# cnc_1_0_0.net
KiCad netlist of a schematic drawn in EAGLE
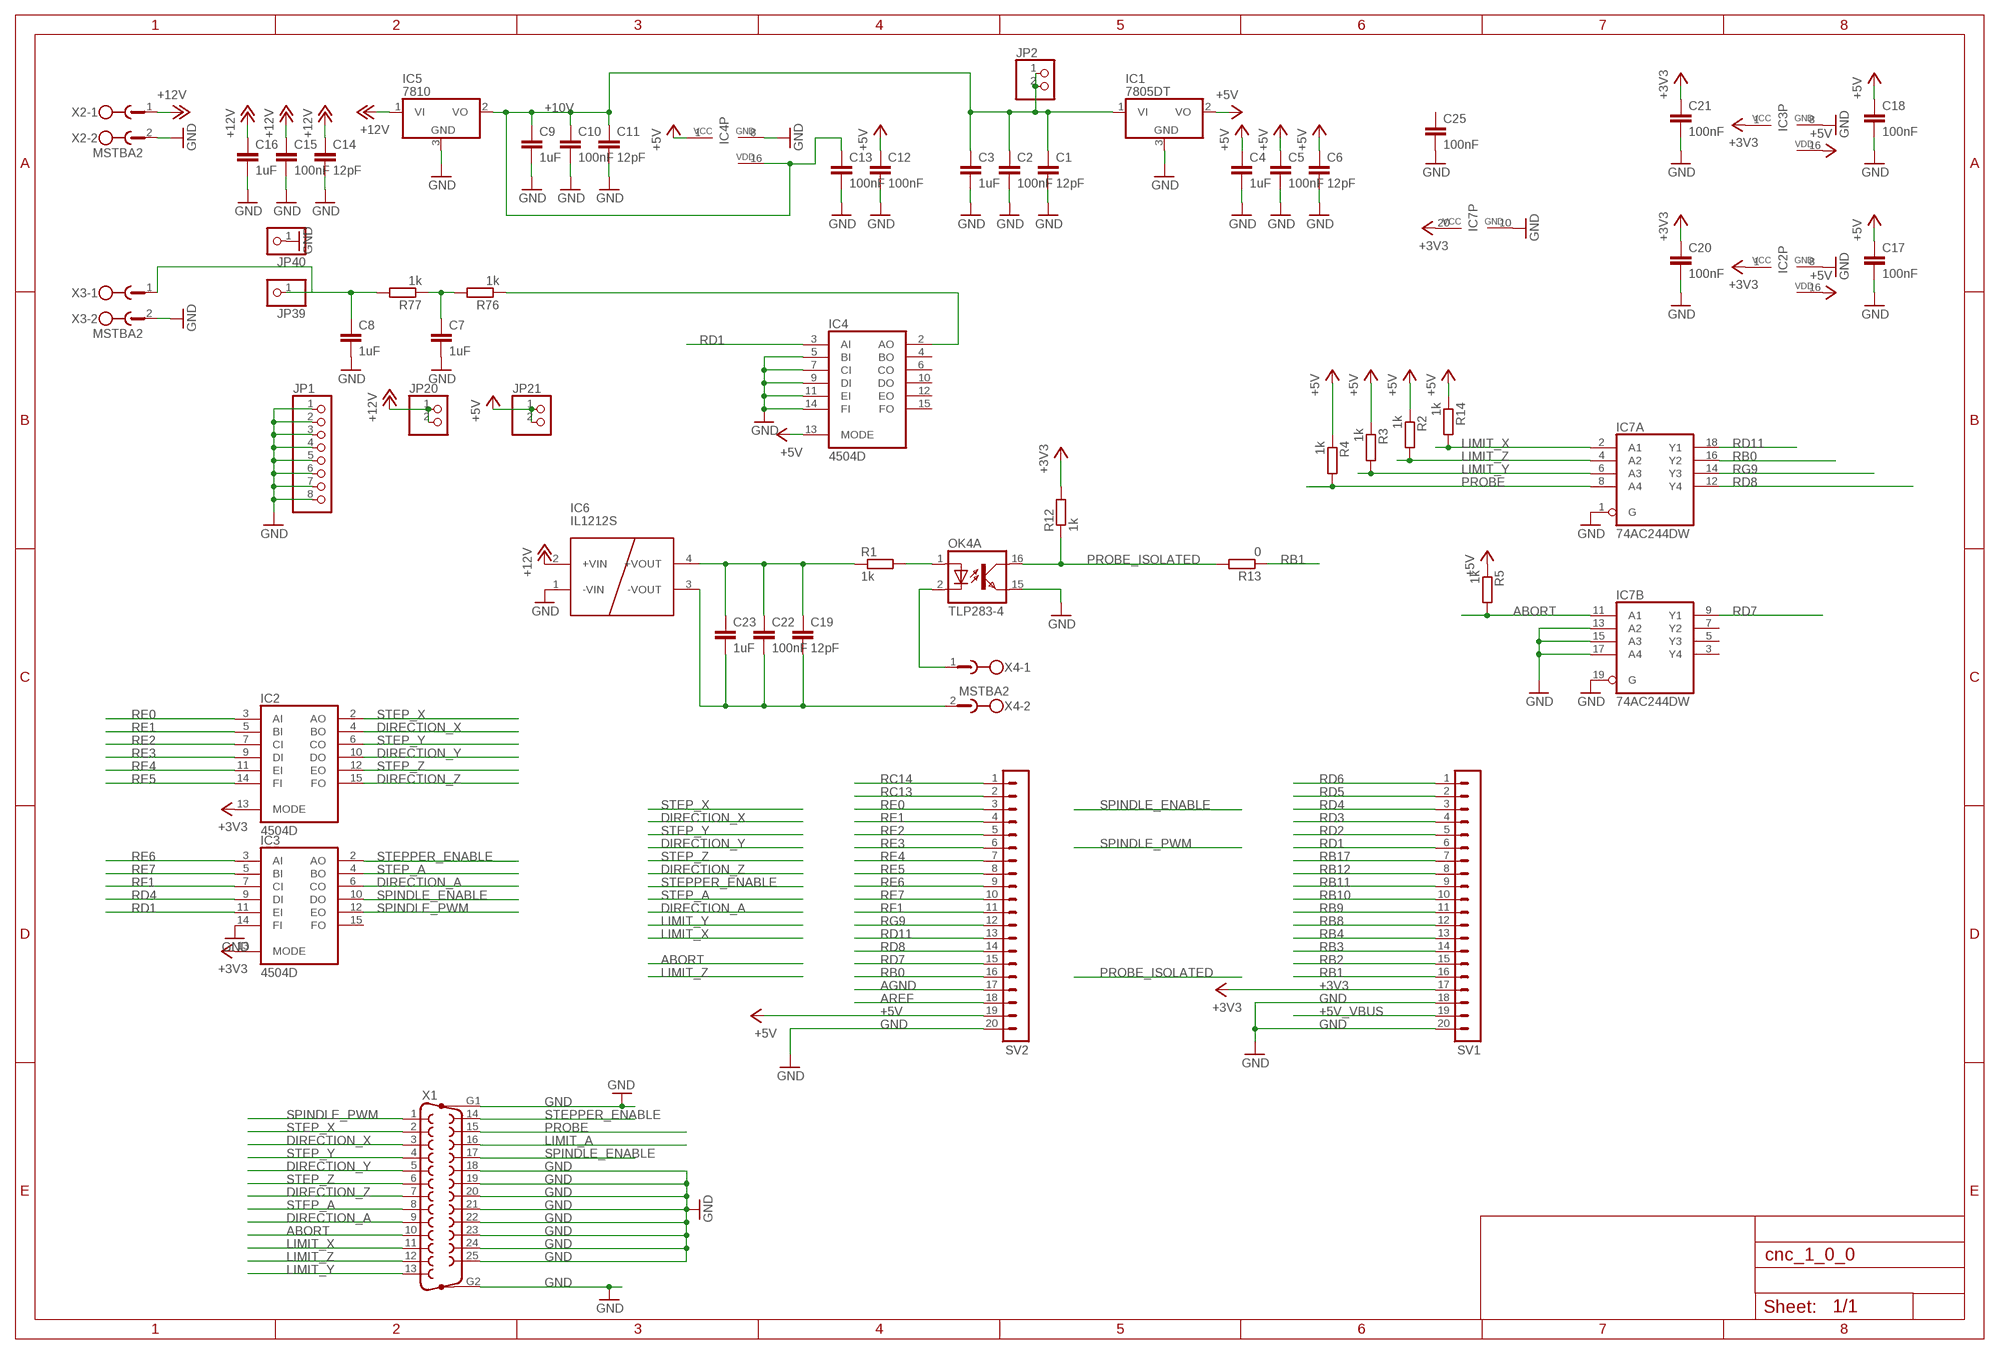
[diagram p0: schematic, sheet 1]

(export (version "E")
  (design (tool "Eeschema 10.0.6"))
  (components
    (comp (ref "C1")
      (value "12pF")
      (footprint "eagle-import:C0805K")
      (libsource (lib "eagle-import") (part "C-EUC0805K"))
    )
    (comp (ref "C2")
      (value "100nF")
      (footprint "eagle-import:C0805K")
      (libsource (lib "eagle-import") (part "C-EUC0805K"))
    )
    (comp (ref "C3")
      (value "1uF")
      (footprint "eagle-import:C0805K")
      (libsource (lib "eagle-import") (part "C-EUC0805K"))
    )
    (comp (ref "C4")
      (value "1uF")
      (footprint "eagle-import:C0805K")
      (libsource (lib "eagle-import") (part "C-EUC0805K"))
    )
    (comp (ref "C5")
      (value "100nF")
      (footprint "eagle-import:C0805K")
      (libsource (lib "eagle-import") (part "C-EUC0805K"))
    )
    (comp (ref "C6")
      (value "12pF")
      (footprint "eagle-import:C0805K")
      (libsource (lib "eagle-import") (part "C-EUC0805K"))
    )
    (comp (ref "C7")
      (value "1uF")
      (footprint "eagle-import:C0805K")
      (libsource (lib "eagle-import") (part "C-EUC0805K"))
    )
    (comp (ref "C8")
      (value "1uF")
      (footprint "eagle-import:C0805K")
      (libsource (lib "eagle-import") (part "C-EUC0805K"))
    )
    (comp (ref "C9")
      (value "1uF")
      (footprint "eagle-import:C0805K")
      (libsource (lib "eagle-import") (part "C-EUC0805K"))
    )
    (comp (ref "C10")
      (value "100nF")
      (footprint "eagle-import:C0805K")
      (libsource (lib "eagle-import") (part "C-EUC0805K"))
    )
    (comp (ref "C11")
      (value "12pF")
      (footprint "eagle-import:C0805K")
      (libsource (lib "eagle-import") (part "C-EUC0805K"))
    )
    (comp (ref "C12")
      (value "100nF")
      (footprint "eagle-import:C0805K")
      (libsource (lib "eagle-import") (part "C-EUC0805K"))
    )
    (comp (ref "C13")
      (value "100nF")
      (footprint "eagle-import:C0805K")
      (libsource (lib "eagle-import") (part "C-EUC0805K"))
    )
    (comp (ref "C14")
      (value "12pF")
      (footprint "eagle-import:C0805K")
      (libsource (lib "eagle-import") (part "C-EUC0805K"))
    )
    (comp (ref "C15")
      (value "100nF")
      (footprint "eagle-import:C0805K")
      (libsource (lib "eagle-import") (part "C-EUC0805K"))
    )
    (comp (ref "C16")
      (value "1uF")
      (footprint "eagle-import:C0805K")
      (libsource (lib "eagle-import") (part "C-EUC0805K"))
    )
    (comp (ref "C17")
      (value "100nF")
      (footprint "eagle-import:C0805K")
      (libsource (lib "eagle-import") (part "C-EUC0805K"))
    )
    (comp (ref "C18")
      (value "100nF")
      (footprint "eagle-import:C0805K")
      (libsource (lib "eagle-import") (part "C-EUC0805K"))
    )
    (comp (ref "C19")
      (value "12pF")
      (footprint "eagle-import:C0805K")
      (libsource (lib "eagle-import") (part "C-EUC0805K"))
    )
    (comp (ref "C20")
      (value "100nF")
      (footprint "eagle-import:C0805K")
      (libsource (lib "eagle-import") (part "C-EUC0805K"))
    )
    (comp (ref "C21")
      (value "100nF")
      (footprint "eagle-import:C0805K")
      (libsource (lib "eagle-import") (part "C-EUC0805K"))
    )
    (comp (ref "C22")
      (value "100nF")
      (footprint "eagle-import:C0805K")
      (libsource (lib "eagle-import") (part "C-EUC0805K"))
    )
    (comp (ref "C23")
      (value "1uF")
      (footprint "eagle-import:C0805K")
      (libsource (lib "eagle-import") (part "C-EUC0805K"))
    )
    (comp (ref "C25")
      (value "100nF")
      (footprint "eagle-import:C0805K")
      (libsource (lib "eagle-import") (part "C-EUC0805K"))
    )
    (comp (ref "IC1")
      (value "7805DT")
      (footprint "eagle-import:TO252")
      (libsource (lib "eagle-import") (part "78DT05"))
    )
    (comp (ref "IC2")
      (value "4504D")
      (footprint "eagle-import:SO16")
      (libsource (lib "eagle-import") (part "4504D"))
    )
    (comp (ref "IC3")
      (value "4504D")
      (footprint "eagle-import:SO16")
      (libsource (lib "eagle-import") (part "4504D"))
    )
    (comp (ref "IC4")
      (value "4504D")
      (footprint "eagle-import:SO16")
      (libsource (lib "eagle-import") (part "4504D"))
    )
    (comp (ref "IC5")
      (value "7810")
      (footprint "eagle-import:TO252")
      (libsource (lib "eagle-import") (part "78DT05"))
    )
    (comp (ref "IC6")
      (value "IL1212S")
      (footprint "eagle-import:SIL4")
      (libsource (lib "eagle-import") (part "IL0512S"))
    )
    (comp (ref "IC7")
      (value "74AC244DW")
      (footprint "eagle-import:SO20W")
      (libsource (lib "eagle-import") (part "74244DWAC"))
    )
    (comp (ref "JP1")
      (value "PINHD-1X8")
      (footprint "eagle-import:1X08")
      (libsource (lib "eagle-import") (part "PINHD-1X8"))
    )
    (comp (ref "JP2")
      (value "PINHD-1X2")
      (footprint "eagle-import:1X02")
      (libsource (lib "eagle-import") (part "PINHD-1X2"))
    )
    (comp (ref "JP20")
      (value "PINHD-1X2")
      (footprint "eagle-import:1X02")
      (libsource (lib "eagle-import") (part "PINHD-1X2"))
    )
    (comp (ref "JP21")
      (value "PINHD-1X2")
      (footprint "eagle-import:1X02")
      (libsource (lib "eagle-import") (part "PINHD-1X2"))
    )
    (comp (ref "JP39")
      (value "PINHD-1X1")
      (footprint "eagle-import:1X01")
      (libsource (lib "eagle-import") (part "PINHD-1X1"))
    )
    (comp (ref "JP40")
      (value "PINHD-1X1")
      (footprint "eagle-import:1X01")
      (libsource (lib "eagle-import") (part "PINHD-1X1"))
    )
    (comp (ref "OK4")
      (value "TLP283-4")
      (footprint "eagle-import:MINI-FLAT-16")
      (libsource (lib "eagle-import") (part "TLP283-4"))
    )
    (comp (ref "R1")
      (value "1k")
      (footprint "eagle-import:R0805")
      (libsource (lib "eagle-import") (part "R-EU_R0805"))
    )
    (comp (ref "R2")
      (value "1k")
      (footprint "eagle-import:R0805")
      (libsource (lib "eagle-import") (part "R-EU_R0805"))
    )
    (comp (ref "R3")
      (value "1k")
      (footprint "eagle-import:R0805")
      (libsource (lib "eagle-import") (part "R-EU_R0805"))
    )
    (comp (ref "R4")
      (value "1k")
      (footprint "eagle-import:R0805")
      (libsource (lib "eagle-import") (part "R-EU_R0805"))
    )
    (comp (ref "R5")
      (value "1k")
      (footprint "eagle-import:R0805")
      (libsource (lib "eagle-import") (part "R-EU_R0805"))
    )
    (comp (ref "R12")
      (value "1k")
      (footprint "eagle-import:R0805")
      (libsource (lib "eagle-import") (part "R-EU_R0805"))
    )
    (comp (ref "R13")
      (value "0")
      (footprint "eagle-import:R0805")
      (libsource (lib "eagle-import") (part "R-EU_R0805"))
    )
    (comp (ref "R14")
      (value "1k")
      (footprint "eagle-import:R0805")
      (libsource (lib "eagle-import") (part "R-EU_R0805"))
    )
    (comp (ref "R76")
      (value "1k")
      (footprint "eagle-import:R0805")
      (libsource (lib "eagle-import") (part "R-EU_R0805"))
    )
    (comp (ref "R77")
      (value "1k")
      (footprint "eagle-import:R0805")
      (libsource (lib "eagle-import") (part "R-EU_R0805"))
    )
    (comp (ref "SV1")
      (value "MA20-1")
      (footprint "eagle-import:MA20-1")
      (libsource (lib "eagle-import") (part "MA20-1"))
    )
    (comp (ref "SV2")
      (value "MA20-1")
      (footprint "eagle-import:MA20-1")
      (libsource (lib "eagle-import") (part "MA20-1"))
    )
    (comp (ref "X1")
      (value "F25HP")
      (footprint "eagle-import:F25HP")
      (libsource (lib "eagle-import") (part "F25HP"))
    )
    (comp (ref "X2")
      (value "MSTBA2")
      (footprint "eagle-import:MSTBA2")
      (fields (field (name "MF") "FARNELL") (field (name "MPN") "1757242"))
      (libsource (lib "eagle-import") (part "MSTBA2"))
    )
    (comp (ref "X3")
      (value "MSTBA2")
      (footprint "eagle-import:MSTBA2")
      (fields
        (field (name "MF") "FARNELL")
        (field (name "MPN") "1757242")
        (field (name "MF_1") "FARNELL")
        (field (name "MPN_1") "1757242")
        (field (name "OC_FARNELL") "3705171")
        (field (name "OC_NEWARK") "71C4161")
      )
      (libsource (lib "eagle-import") (part "MSTBA2"))
    )
    (comp (ref "X4")
      (value "MSTBA2")
      (footprint "eagle-import:MSTBA2")
      (fields
        (field (name "MF") "FARNELL")
        (field (name "MPN") "1757242")
        (field (name "MF_1") "FARNELL")
        (field (name "MPN_1") "1757242")
        (field (name "OC_FARNELL") "3705171")
        (field (name "OC_NEWARK") "71C4161")
      )
      (libsource (lib "eagle-import") (part "MSTBA2"))
    )
  )
  (nets
    (net (code "1") (name "+3V3") (class "Default")
      (node (ref "C20") (pin "1") (pinfunction "1_1") (pintype "passive"))
      (node (ref "C21") (pin "1") (pinfunction "1_1") (pintype "passive"))
      (node (ref "IC2") (pin "1") (pinfunction "VCC_1") (pintype "power_in"))
      (node (ref "IC2") (pin "13") (pinfunction "MODE_13") (pintype "input"))
      (node (ref "IC3") (pin "1") (pinfunction "VCC_1") (pintype "power_in"))
      (node (ref "IC3") (pin "13") (pinfunction "MODE_13") (pintype "input"))
      (node (ref "IC7") (pin "20") (pinfunction "VCC_20") (pintype "power_in"))
      (node (ref "R12") (pin "2") (pinfunction "2_2") (pintype "passive"))
      (node (ref "SV1") (pin "17") (pinfunction "17_17") (pintype "passive"))
    )
    (net (code "2") (name "+5V") (class "Default")
      (node (ref "C12") (pin "1") (pinfunction "1_1") (pintype "passive"))
      (node (ref "C17") (pin "1") (pinfunction "1_1") (pintype "passive"))
      (node (ref "C18") (pin "1") (pinfunction "1_1") (pintype "passive"))
      (node (ref "C4") (pin "1") (pinfunction "1_1") (pintype "passive"))
      (node (ref "C5") (pin "1") (pinfunction "1_1") (pintype "passive"))
      (node (ref "C6") (pin "1") (pinfunction "1_1") (pintype "passive"))
      (node (ref "IC1") (pin "2") (pinfunction "VO_2") (pintype "passive"))
      (node (ref "IC2") (pin "16") (pinfunction "VDD_16") (pintype "power_in"))
      (node (ref "IC3") (pin "16") (pinfunction "VDD_16") (pintype "power_in"))
      (node (ref "IC4") (pin "1") (pinfunction "VCC_1") (pintype "power_in"))
      (node (ref "IC4") (pin "13") (pinfunction "MODE_13") (pintype "input"))
      (node (ref "JP21") (pin "1") (pinfunction "1_1") (pintype "passive"))
      (node (ref "JP21") (pin "2") (pinfunction "2_2") (pintype "passive"))
      (node (ref "R14") (pin "1") (pinfunction "1_1") (pintype "passive"))
      (node (ref "R2") (pin "1") (pinfunction "1_1") (pintype "passive"))
      (node (ref "R3") (pin "1") (pinfunction "1_1") (pintype "passive"))
      (node (ref "R4") (pin "1") (pinfunction "1_1") (pintype "passive"))
      (node (ref "R5") (pin "1") (pinfunction "1_1") (pintype "passive"))
      (node (ref "SV2") (pin "19") (pinfunction "19_19") (pintype "passive"))
    )
    (net (code "3") (name "+12V") (class "Default")
      (node (ref "C14") (pin "1") (pinfunction "1_1") (pintype "passive"))
      (node (ref "C15") (pin "1") (pinfunction "1_1") (pintype "passive"))
      (node (ref "C16") (pin "1") (pinfunction "1_1") (pintype "passive"))
      (node (ref "IC5") (pin "1") (pinfunction "VI_1") (pintype "input"))
      (node (ref "IC6") (pin "2") (pinfunction "+VIN_2") (pintype "bidirectional"))
      (node (ref "JP20") (pin "1") (pinfunction "1_1") (pintype "passive"))
      (node (ref "JP20") (pin "2") (pinfunction "2_2") (pintype "passive"))
      (node (ref "X2") (pin "1") (pinfunction "1_1") (pintype "passive"))
    )
    (net (code "4") (name "/+5V_VBUS") (class "Default")
      (node (ref "SV1") (pin "19") (pinfunction "19_19") (pintype "passive"))
    )
    (net (code "5") (name "/+10V") (class "Default")
      (node (ref "C1") (pin "1") (pinfunction "1_1") (pintype "passive"))
      (node (ref "C10") (pin "1") (pinfunction "1_1") (pintype "passive"))
      (node (ref "C11") (pin "1") (pinfunction "1_1") (pintype "passive"))
      (node (ref "C13") (pin "1") (pinfunction "1_1") (pintype "passive"))
      (node (ref "C2") (pin "1") (pinfunction "1_1") (pintype "passive"))
      (node (ref "C3") (pin "1") (pinfunction "1_1") (pintype "passive"))
      (node (ref "C9") (pin "1") (pinfunction "1_1") (pintype "passive"))
      (node (ref "IC1") (pin "1") (pinfunction "VI_1") (pintype "input"))
      (node (ref "IC4") (pin "16") (pinfunction "VDD_16") (pintype "power_in"))
      (node (ref "IC5") (pin "2") (pinfunction "VO_2") (pintype "passive"))
      (node (ref "JP2") (pin "1") (pinfunction "1_1") (pintype "passive"))
      (node (ref "JP2") (pin "2") (pinfunction "2_2") (pintype "passive"))
    )
    (net (code "6") (name "/ABORT") (class "Default")
      (node (ref "IC7") (pin "11") (pinfunction "A1_11") (pintype "input"))
      (node (ref "R5") (pin "2") (pinfunction "2_2") (pintype "passive"))
      (node (ref "X1") (pin "10") (pinfunction "10_10") (pintype "passive"))
    )
    (net (code "7") (name "/AGND") (class "Default")
      (node (ref "SV2") (pin "17") (pinfunction "17_17") (pintype "passive"))
    )
    (net (code "8") (name "/AREF") (class "Default")
      (node (ref "SV2") (pin "18") (pinfunction "18_18") (pintype "passive"))
    )
    (net (code "9") (name "/DIRECTION_A") (class "Default")
      (node (ref "IC3") (pin "6") (pinfunction "CO_6") (pintype "output"))
      (node (ref "X1") (pin "9") (pinfunction "9_9") (pintype "passive"))
    )
    (net (code "10") (name "/DIRECTION_X") (class "Default")
      (node (ref "IC2") (pin "4") (pinfunction "BO_4") (pintype "output"))
      (node (ref "X1") (pin "3") (pinfunction "3_3") (pintype "passive"))
    )
    (net (code "11") (name "/DIRECTION_Y") (class "Default")
      (node (ref "IC2") (pin "10") (pinfunction "DO_10") (pintype "output"))
      (node (ref "X1") (pin "5") (pinfunction "5_5") (pintype "passive"))
    )
    (net (code "12") (name "/DIRECTION_Z") (class "Default")
      (node (ref "IC2") (pin "15") (pinfunction "FO_15") (pintype "output"))
      (node (ref "X1") (pin "7") (pinfunction "7_7") (pintype "passive"))
    )
    (net (code "13") (name "/LIMIT_A") (class "Default")
      (node (ref "X1") (pin "16") (pinfunction "16_16") (pintype "passive"))
    )
    (net (code "14") (name "/LIMIT_X") (class "Default")
      (node (ref "IC7") (pin "2") (pinfunction "A1_2") (pintype "input"))
      (node (ref "R14") (pin "2") (pinfunction "2_2") (pintype "passive"))
      (node (ref "X1") (pin "11") (pinfunction "11_11") (pintype "passive"))
    )
    (net (code "15") (name "/LIMIT_Y") (class "Default")
      (node (ref "IC7") (pin "6") (pinfunction "A3_6") (pintype "input"))
      (node (ref "R3") (pin "2") (pinfunction "2_2") (pintype "passive"))
      (node (ref "X1") (pin "13") (pinfunction "13_13") (pintype "passive"))
    )
    (net (code "16") (name "/LIMIT_Z") (class "Default")
      (node (ref "IC7") (pin "4") (pinfunction "A2_4") (pintype "input"))
      (node (ref "R2") (pin "2") (pinfunction "2_2") (pintype "passive"))
      (node (ref "X1") (pin "12") (pinfunction "12_12") (pintype "passive"))
    )
    (net (code "17") (name "/PROBE") (class "Default")
      (node (ref "IC7") (pin "8") (pinfunction "A4_8") (pintype "input"))
      (node (ref "R4") (pin "2") (pinfunction "2_2") (pintype "passive"))
      (node (ref "X1") (pin "15") (pinfunction "15_15") (pintype "passive"))
    )
    (net (code "18") (name "/PROBE_ISOLATED") (class "Default")
      (node (ref "OK4") (pin "16") (pinfunction "COL_16") (pintype "passive"))
      (node (ref "R12") (pin "1") (pinfunction "1_1") (pintype "passive"))
      (node (ref "R13") (pin "2") (pinfunction "2_2") (pintype "passive"))
    )
    (net (code "19") (name "/RB0") (class "Default")
      (node (ref "IC7") (pin "16") (pinfunction "Y2_16") (pintype "tri_state"))
      (node (ref "SV2") (pin "16") (pinfunction "16_16") (pintype "passive"))
    )
    (net (code "20") (name "/RB1") (class "Default")
      (node (ref "R13") (pin "1") (pinfunction "1_1") (pintype "passive"))
      (node (ref "SV1") (pin "16") (pinfunction "16_16") (pintype "passive"))
    )
    (net (code "21") (name "/RB2") (class "Default")
      (node (ref "SV1") (pin "15") (pinfunction "15_15") (pintype "passive"))
    )
    (net (code "22") (name "/RB3") (class "Default")
      (node (ref "SV1") (pin "14") (pinfunction "14_14") (pintype "passive"))
    )
    (net (code "23") (name "/RB4") (class "Default")
      (node (ref "SV1") (pin "13") (pinfunction "13_13") (pintype "passive"))
    )
    (net (code "24") (name "/RB8") (class "Default")
      (node (ref "SV1") (pin "12") (pinfunction "12_12") (pintype "passive"))
    )
    (net (code "25") (name "/RB9") (class "Default")
      (node (ref "SV1") (pin "11") (pinfunction "11_11") (pintype "passive"))
    )
    (net (code "26") (name "/RB10") (class "Default")
      (node (ref "SV1") (pin "10") (pinfunction "10_10") (pintype "passive"))
    )
    (net (code "27") (name "/RB11") (class "Default")
      (node (ref "SV1") (pin "9") (pinfunction "9_9") (pintype "passive"))
    )
    (net (code "28") (name "/RB12") (class "Default")
      (node (ref "SV1") (pin "8") (pinfunction "8_8") (pintype "passive"))
    )
    (net (code "29") (name "/RB17") (class "Default")
      (node (ref "SV1") (pin "7") (pinfunction "7_7") (pintype "passive"))
    )
    (net (code "30") (name "/RC13") (class "Default")
      (node (ref "SV2") (pin "2") (pinfunction "2_2") (pintype "passive"))
    )
    (net (code "31") (name "/RC14") (class "Default")
      (node (ref "SV2") (pin "1") (pinfunction "1_1") (pintype "passive"))
    )
    (net (code "32") (name "/RD1") (class "Default")
      (node (ref "IC3") (pin "11") (pinfunction "EI_11") (pintype "input"))
      (node (ref "IC4") (pin "3") (pinfunction "AI_3") (pintype "input"))
      (node (ref "SV1") (pin "6") (pinfunction "6_6") (pintype "passive"))
    )
    (net (code "33") (name "/RD2") (class "Default")
      (node (ref "SV1") (pin "5") (pinfunction "5_5") (pintype "passive"))
    )
    (net (code "34") (name "/RD3") (class "Default")
      (node (ref "SV1") (pin "4") (pinfunction "4_4") (pintype "passive"))
    )
    (net (code "35") (name "/RD4") (class "Default")
      (node (ref "IC3") (pin "9") (pinfunction "DI_9") (pintype "input"))
      (node (ref "SV1") (pin "3") (pinfunction "3_3") (pintype "passive"))
    )
    (net (code "36") (name "/RD5") (class "Default")
      (node (ref "SV1") (pin "2") (pinfunction "2_2") (pintype "passive"))
    )
    (net (code "37") (name "/RD6") (class "Default")
      (node (ref "SV1") (pin "1") (pinfunction "1_1") (pintype "passive"))
    )
    (net (code "38") (name "/RD7") (class "Default")
      (node (ref "IC7") (pin "9") (pinfunction "Y1_9") (pintype "tri_state"))
      (node (ref "SV2") (pin "15") (pinfunction "15_15") (pintype "passive"))
    )
    (net (code "39") (name "/RD8") (class "Default")
      (node (ref "IC7") (pin "12") (pinfunction "Y4_12") (pintype "tri_state"))
      (node (ref "SV2") (pin "14") (pinfunction "14_14") (pintype "passive"))
    )
    (net (code "40") (name "/RD11") (class "Default")
      (node (ref "IC7") (pin "18") (pinfunction "Y1_18") (pintype "tri_state"))
      (node (ref "SV2") (pin "13") (pinfunction "13_13") (pintype "passive"))
    )
    (net (code "41") (name "/RE0") (class "Default")
      (node (ref "IC2") (pin "3") (pinfunction "AI_3") (pintype "input"))
      (node (ref "SV2") (pin "3") (pinfunction "3_3") (pintype "passive"))
    )
    (net (code "42") (name "/RE1") (class "Default")
      (node (ref "IC2") (pin "5") (pinfunction "BI_5") (pintype "input"))
      (node (ref "SV2") (pin "4") (pinfunction "4_4") (pintype "passive"))
    )
    (net (code "43") (name "/RE2") (class "Default")
      (node (ref "IC2") (pin "7") (pinfunction "CI_7") (pintype "input"))
      (node (ref "SV2") (pin "5") (pinfunction "5_5") (pintype "passive"))
    )
    (net (code "44") (name "/RE3") (class "Default")
      (node (ref "IC2") (pin "9") (pinfunction "DI_9") (pintype "input"))
      (node (ref "SV2") (pin "6") (pinfunction "6_6") (pintype "passive"))
    )
    (net (code "45") (name "/RE4") (class "Default")
      (node (ref "IC2") (pin "11") (pinfunction "EI_11") (pintype "input"))
      (node (ref "SV2") (pin "7") (pinfunction "7_7") (pintype "passive"))
    )
    (net (code "46") (name "/RE5") (class "Default")
      (node (ref "IC2") (pin "14") (pinfunction "FI_14") (pintype "input"))
      (node (ref "SV2") (pin "8") (pinfunction "8_8") (pintype "passive"))
    )
    (net (code "47") (name "/RE6") (class "Default")
      (node (ref "IC3") (pin "3") (pinfunction "AI_3") (pintype "input"))
      (node (ref "SV2") (pin "9") (pinfunction "9_9") (pintype "passive"))
    )
    (net (code "48") (name "/RE7") (class "Default")
      (node (ref "IC3") (pin "5") (pinfunction "BI_5") (pintype "input"))
      (node (ref "SV2") (pin "10") (pinfunction "10_10") (pintype "passive"))
    )
    (net (code "49") (name "/RF1") (class "Default")
      (node (ref "IC3") (pin "7") (pinfunction "CI_7") (pintype "input"))
      (node (ref "SV2") (pin "11") (pinfunction "11_11") (pintype "passive"))
    )
    (net (code "50") (name "/RG9") (class "Default")
      (node (ref "IC7") (pin "14") (pinfunction "Y3_14") (pintype "tri_state"))
      (node (ref "SV2") (pin "12") (pinfunction "12_12") (pintype "passive"))
    )
    (net (code "51") (name "/SPINDLE_ENABLE") (class "Default")
      (node (ref "IC3") (pin "10") (pinfunction "DO_10") (pintype "output"))
      (node (ref "X1") (pin "17") (pinfunction "17_17") (pintype "passive"))
    )
    (net (code "52") (name "/SPINDLE_PWM") (class "Default")
      (node (ref "IC3") (pin "12") (pinfunction "EO_12") (pintype "output"))
      (node (ref "X1") (pin "1") (pinfunction "1_1") (pintype "passive"))
    )
    (net (code "53") (name "/STEPPER_ENABLE") (class "Default")
      (node (ref "IC3") (pin "2") (pinfunction "AO_2") (pintype "output"))
      (node (ref "X1") (pin "14") (pinfunction "14_14") (pintype "passive"))
    )
    (net (code "54") (name "/STEP_A") (class "Default")
      (node (ref "IC3") (pin "4") (pinfunction "BO_4") (pintype "output"))
      (node (ref "X1") (pin "8") (pinfunction "8_8") (pintype "passive"))
    )
    (net (code "55") (name "/STEP_X") (class "Default")
      (node (ref "IC2") (pin "2") (pinfunction "AO_2") (pintype "output"))
      (node (ref "X1") (pin "2") (pinfunction "2_2") (pintype "passive"))
    )
    (net (code "56") (name "/STEP_Y") (class "Default")
      (node (ref "IC2") (pin "6") (pinfunction "CO_6") (pintype "output"))
      (node (ref "X1") (pin "4") (pinfunction "4_4") (pintype "passive"))
    )
    (net (code "57") (name "/STEP_Z") (class "Default")
      (node (ref "IC2") (pin "12") (pinfunction "EO_12") (pintype "output"))
      (node (ref "X1") (pin "6") (pinfunction "6_6") (pintype "passive"))
    )
    (net (code "58") (name "GND") (class "Default")
      (node (ref "C1") (pin "2") (pinfunction "2_2") (pintype "passive"))
      (node (ref "C10") (pin "2") (pinfunction "2_2") (pintype "passive"))
      (node (ref "C11") (pin "2") (pinfunction "2_2") (pintype "passive"))
      (node (ref "C12") (pin "2") (pinfunction "2_2") (pintype "passive"))
      (node (ref "C13") (pin "2") (pinfunction "2_2") (pintype "passive"))
      (node (ref "C14") (pin "2") (pinfunction "2_2") (pintype "passive"))
      (node (ref "C15") (pin "2") (pinfunction "2_2") (pintype "passive"))
      (node (ref "C16") (pin "2") (pinfunction "2_2") (pintype "passive"))
      (node (ref "C17") (pin "2") (pinfunction "2_2") (pintype "passive"))
      (node (ref "C18") (pin "2") (pinfunction "2_2") (pintype "passive"))
      (node (ref "C2") (pin "2") (pinfunction "2_2") (pintype "passive"))
      (node (ref "C20") (pin "2") (pinfunction "2_2") (pintype "passive"))
      (node (ref "C21") (pin "2") (pinfunction "2_2") (pintype "passive"))
      (node (ref "C25") (pin "2") (pinfunction "2_2") (pintype "passive"))
      (node (ref "C3") (pin "2") (pinfunction "2_2") (pintype "passive"))
      (node (ref "C4") (pin "2") (pinfunction "2_2") (pintype "passive"))
      (node (ref "C5") (pin "2") (pinfunction "2_2") (pintype "passive"))
      (node (ref "C6") (pin "2") (pinfunction "2_2") (pintype "passive"))
      (node (ref "C7") (pin "2") (pinfunction "2_2") (pintype "passive"))
      (node (ref "C8") (pin "2") (pinfunction "2_2") (pintype "passive"))
      (node (ref "C9") (pin "2") (pinfunction "2_2") (pintype "passive"))
      (node (ref "IC1") (pin "3") (pinfunction "GND_3") (pintype "passive"))
      (node (ref "IC2") (pin "8") (pinfunction "GND_8") (pintype "power_in"))
      (node (ref "IC3") (pin "14") (pinfunction "FI_14") (pintype "input"))
      (node (ref "IC3") (pin "8") (pinfunction "GND_8") (pintype "power_in"))
      (node (ref "IC4") (pin "11") (pinfunction "EI_11") (pintype "input"))
      (node (ref "IC4") (pin "14") (pinfunction "FI_14") (pintype "input"))
      (node (ref "IC4") (pin "5") (pinfunction "BI_5") (pintype "input"))
      (node (ref "IC4") (pin "7") (pinfunction "CI_7") (pintype "input"))
      (node (ref "IC4") (pin "8") (pinfunction "GND_8") (pintype "power_in"))
      (node (ref "IC4") (pin "9") (pinfunction "DI_9") (pintype "input"))
      (node (ref "IC5") (pin "3") (pinfunction "GND_3") (pintype "passive"))
      (node (ref "IC6") (pin "1") (pinfunction "-VIN_1") (pintype "bidirectional"))
      (node (ref "IC7") (pin "1") (pinfunction "G_1") (pintype "input"))
      (node (ref "IC7") (pin "10") (pinfunction "GND_10") (pintype "power_in"))
      (node (ref "IC7") (pin "13") (pinfunction "A2_13") (pintype "input"))
      (node (ref "IC7") (pin "15") (pinfunction "A3_15") (pintype "input"))
      (node (ref "IC7") (pin "17") (pinfunction "A4_17") (pintype "input"))
      (node (ref "IC7") (pin "19") (pinfunction "G_19") (pintype "input"))
      (node (ref "JP1") (pin "1") (pinfunction "1_1") (pintype "passive"))
      (node (ref "JP1") (pin "2") (pinfunction "2_2") (pintype "passive"))
      (node (ref "JP1") (pin "3") (pinfunction "3_3") (pintype "passive"))
      (node (ref "JP1") (pin "4") (pinfunction "4_4") (pintype "passive"))
      (node (ref "JP1") (pin "5") (pinfunction "5_5") (pintype "passive"))
      (node (ref "JP1") (pin "6") (pinfunction "6_6") (pintype "passive"))
      (node (ref "JP1") (pin "7") (pinfunction "7_7") (pintype "passive"))
      (node (ref "JP1") (pin "8") (pinfunction "8_8") (pintype "passive"))
      (node (ref "JP40") (pin "1") (pinfunction "1_1") (pintype "passive"))
      (node (ref "OK4") (pin "15") (pinfunction "EMIT_15") (pintype "passive"))
      (node (ref "SV1") (pin "18") (pinfunction "18_18") (pintype "passive"))
      (node (ref "SV1") (pin "20") (pinfunction "20_20") (pintype "passive"))
      (node (ref "SV2") (pin "20") (pinfunction "20_20") (pintype "passive"))
      (node (ref "X1") (pin "18") (pinfunction "18_18") (pintype "passive"))
      (node (ref "X1") (pin "19") (pinfunction "19_19") (pintype "passive"))
      (node (ref "X1") (pin "20") (pinfunction "20_20") (pintype "passive"))
      (node (ref "X1") (pin "21") (pinfunction "21_21") (pintype "passive"))
      (node (ref "X1") (pin "22") (pinfunction "22_22") (pintype "passive"))
      (node (ref "X1") (pin "23") (pinfunction "23_23") (pintype "passive"))
      (node (ref "X1") (pin "24") (pinfunction "24_24") (pintype "passive"))
      (node (ref "X1") (pin "25") (pinfunction "25_25") (pintype "passive"))
      (node (ref "X1") (pin "G1") (pinfunction "G1_G1") (pintype "passive"))
      (node (ref "X1") (pin "G2") (pinfunction "G2_G2") (pintype "passive"))
      (node (ref "X2") (pin "2") (pinfunction "1_2") (pintype "passive"))
      (node (ref "X3") (pin "2") (pinfunction "1_2") (pintype "passive"))
    )
    (net (code "59") (name "Net-(C7-Pad1)") (class "Default")
      (node (ref "C7") (pin "1") (pinfunction "1_1") (pintype "passive"))
      (node (ref "R76") (pin "2") (pinfunction "2_2") (pintype "passive"))
      (node (ref "R77") (pin "1") (pinfunction "1_1") (pintype "passive"))
    )
    (net (code "60") (name "Net-(C8-Pad1)") (class "Default")
      (node (ref "C8") (pin "1") (pinfunction "1_1") (pintype "passive"))
      (node (ref "JP39") (pin "1") (pinfunction "1_1") (pintype "passive"))
      (node (ref "R77") (pin "2") (pinfunction "2_2") (pintype "passive"))
      (node (ref "X3") (pin "1") (pinfunction "1_1") (pintype "passive"))
    )
    (net (code "61") (name "Net-(IC4A-AO)") (class "Default")
      (node (ref "IC4") (pin "2") (pinfunction "AO_2") (pintype "output"))
      (node (ref "R76") (pin "1") (pinfunction "1_1") (pintype "passive"))
    )
    (net (code "62") (name "Net-(IC6-+VOUT)") (class "Default")
      (node (ref "C19") (pin "1") (pinfunction "1_1") (pintype "passive"))
      (node (ref "C22") (pin "1") (pinfunction "1_1") (pintype "passive"))
      (node (ref "C23") (pin "1") (pinfunction "1_1") (pintype "passive"))
      (node (ref "IC6") (pin "4") (pinfunction "+VOUT_4") (pintype "bidirectional"))
      (node (ref "R1") (pin "1") (pinfunction "1_1") (pintype "passive"))
    )
    (net (code "63") (name "Net-(IC6--VOUT)") (class "Default")
      (node (ref "C19") (pin "2") (pinfunction "2_2") (pintype "passive"))
      (node (ref "C22") (pin "2") (pinfunction "2_2") (pintype "passive"))
      (node (ref "C23") (pin "2") (pinfunction "2_2") (pintype "passive"))
      (node (ref "IC6") (pin "3") (pinfunction "-VOUT_3") (pintype "bidirectional"))
      (node (ref "X4") (pin "2") (pinfunction "1_2") (pintype "passive"))
    )
    (net (code "64") (name "Net-(OK4A-A)") (class "Default")
      (node (ref "OK4") (pin "1") (pinfunction "A_1") (pintype "passive"))
      (node (ref "R1") (pin "2") (pinfunction "2_2") (pintype "passive"))
    )
    (net (code "65") (name "Net-(OK4A-C)") (class "Default")
      (node (ref "OK4") (pin "2") (pinfunction "C_2") (pintype "passive"))
      (node (ref "X4") (pin "1") (pinfunction "1_1") (pintype "passive"))
    )
    (net (code "66") (name "unconnected-(C25-Pad1)") (class "Default")
      (node (ref "C25") (pin "1") (pinfunction "1_1") (pintype "passive"))
    )
    (net (code "67") (name "unconnected-(IC3A-FO-Pad15)") (class "Default")
      (node (ref "IC3") (pin "15") (pinfunction "FO_15") (pintype "output"))
    )
    (net (code "68") (name "unconnected-(IC4A-BO-Pad4)") (class "Default")
      (node (ref "IC4") (pin "4") (pinfunction "BO_4") (pintype "output"))
    )
    (net (code "69") (name "unconnected-(IC4A-CO-Pad6)") (class "Default")
      (node (ref "IC4") (pin "6") (pinfunction "CO_6") (pintype "output"))
    )
    (net (code "70") (name "unconnected-(IC4A-DO-Pad10)") (class "Default")
      (node (ref "IC4") (pin "10") (pinfunction "DO_10") (pintype "output"))
    )
    (net (code "71") (name "unconnected-(IC4A-EO-Pad12)") (class "Default")
      (node (ref "IC4") (pin "12") (pinfunction "EO_12") (pintype "output"))
    )
    (net (code "72") (name "unconnected-(IC4A-FO-Pad15)") (class "Default")
      (node (ref "IC4") (pin "15") (pinfunction "FO_15") (pintype "output"))
    )
    (net (code "73") (name "unconnected-(IC7B-Y2-Pad7)") (class "Default")
      (node (ref "IC7") (pin "7") (pinfunction "Y2_7") (pintype "tri_state"))
    )
    (net (code "74") (name "unconnected-(IC7B-Y3-Pad5)") (class "Default")
      (node (ref "IC7") (pin "5") (pinfunction "Y3_5") (pintype "tri_state"))
    )
    (net (code "75") (name "unconnected-(IC7B-Y4-Pad3)") (class "Default")
      (node (ref "IC7") (pin "3") (pinfunction "Y4_3") (pintype "tri_state"))
    )
  )
)
